# Qwiic_Chirp_101.net
KiCad netlist of a schematic drawn in EAGLE
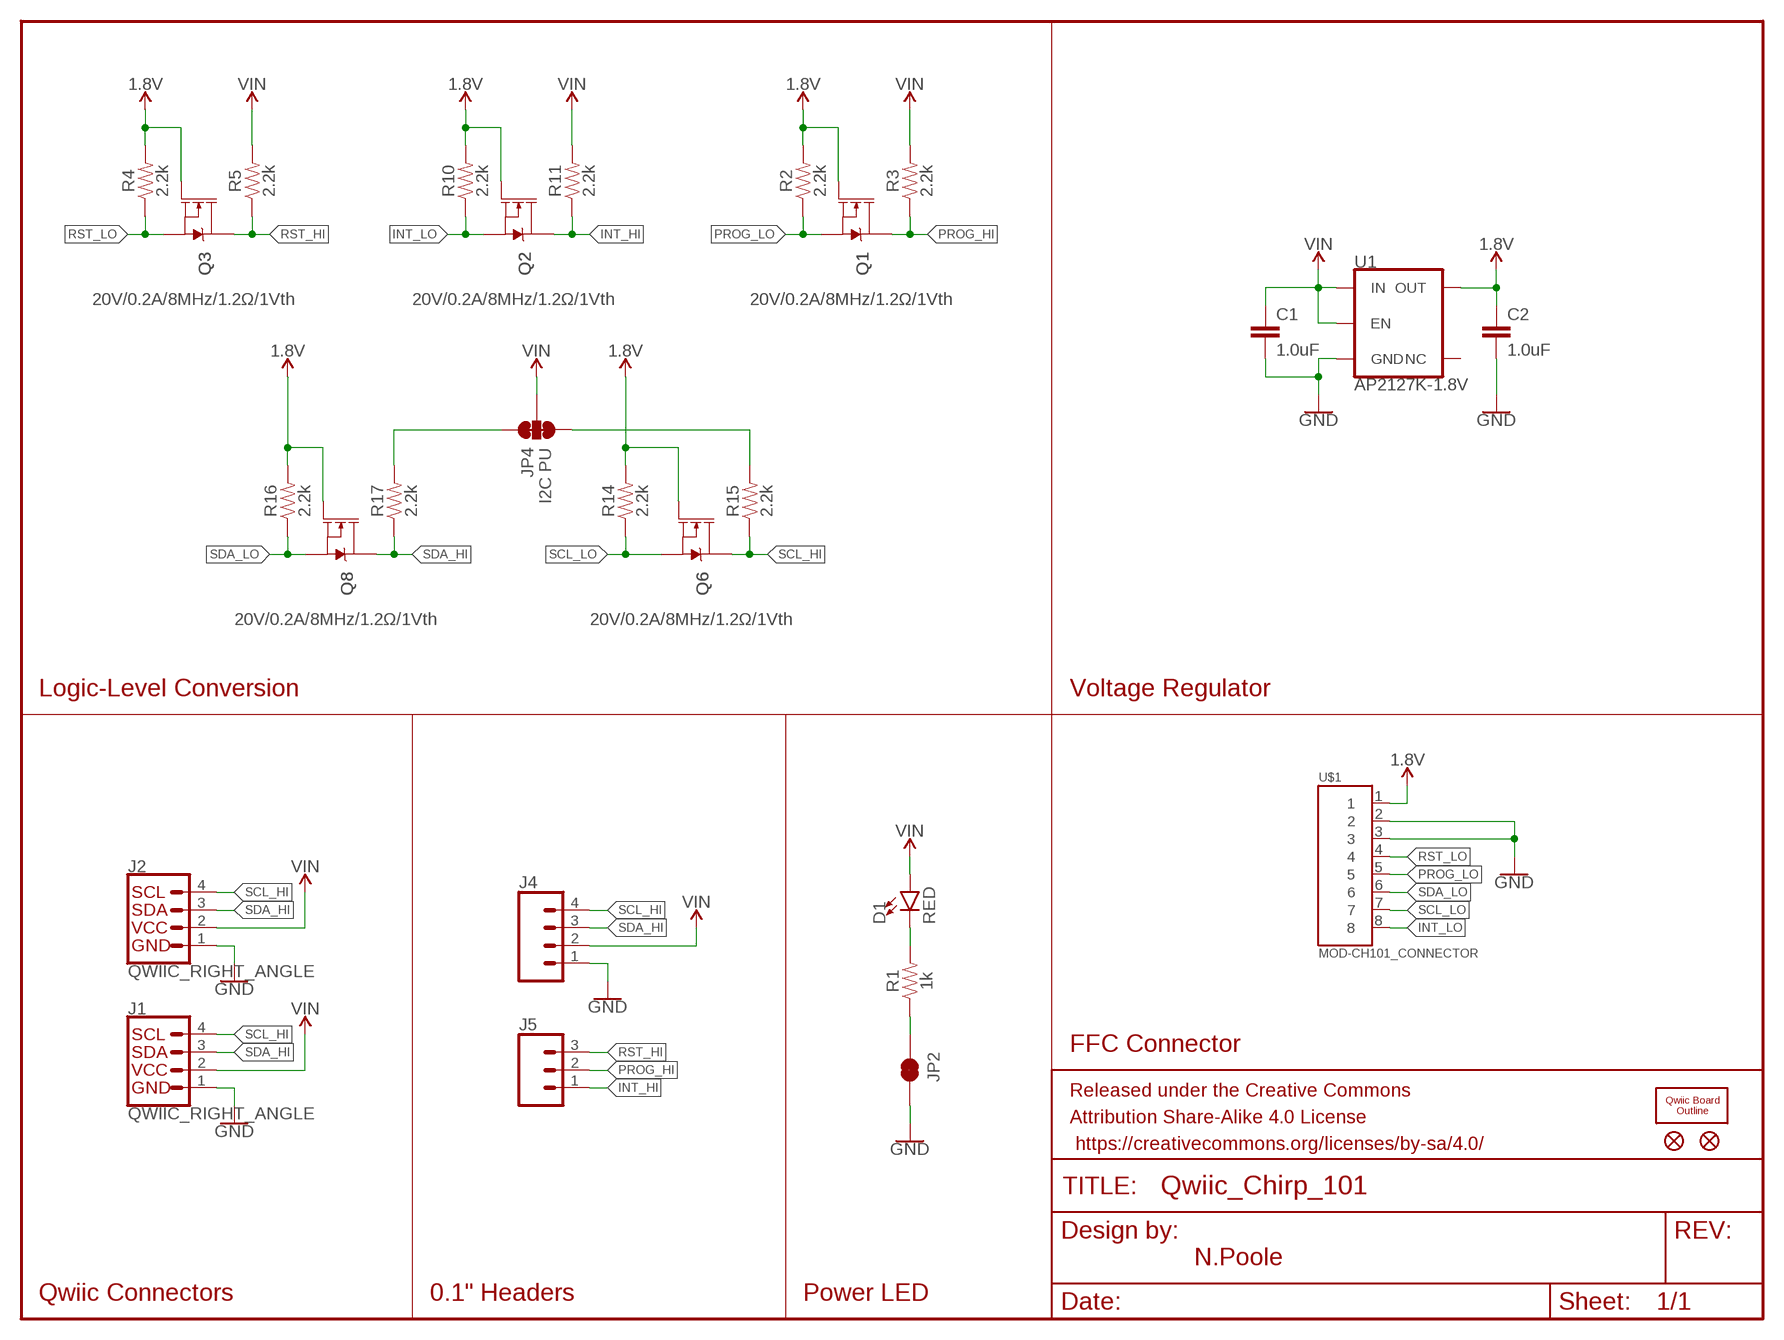
[diagram p0: schematic, sheet 1]

(export (version "E")
  (design (tool "Eeschema 10.0.6"))
  (components
    (comp (ref "C1")
      (value "1.0uF")
      (footprint "eagle-import:0603")
      (libsource (lib "eagle-import") (part "1.0UF-0603-16V-10%"))
    )
    (comp (ref "C2")
      (value "1.0uF")
      (footprint "eagle-import:0603")
      (libsource (lib "eagle-import") (part "1.0UF-0603-16V-10%"))
    )
    (comp (ref "D1")
      (value "RED")
      (footprint "eagle-import:LED-0603")
      (libsource (lib "eagle-import") (part "LED-RED0603"))
    )
    (comp (ref "FD1")
      (value "FIDUCIALUFIDUCIAL")
      (footprint "eagle-import:FIDUCIAL-MICRO")
      (libsource (lib "eagle-import") (part "FIDUCIALUFIDUCIAL"))
    )
    (comp (ref "FD2")
      (value "FIDUCIALUFIDUCIAL")
      (footprint "eagle-import:FIDUCIAL-MICRO")
      (libsource (lib "eagle-import") (part "FIDUCIALUFIDUCIAL"))
    )
    (comp (ref "FRAME1")
      (value "FRAME-LETTERNO_PACKAGE")
      (footprint "eagle-import:DUMMY")
      (fields (field (name "DESIGNER") "Nobody"))
      (libsource (lib "eagle-import") (part "FRAME-LETTERNO_PACKAGE"))
    )
    (comp (ref "J1")
      (value "QWIIC_RIGHT_ANGLE")
      (footprint "eagle-import:JST04_1MM_RA")
      (libsource (lib "eagle-import") (part "QWIIC_CONNECTORJS-1MM"))
    )
    (comp (ref "J2")
      (value "QWIIC_RIGHT_ANGLE")
      (footprint "eagle-import:JST04_1MM_RA")
      (libsource (lib "eagle-import") (part "QWIIC_CONNECTORJS-1MM"))
    )
    (comp (ref "J4")
      (value "CONN_041X04_NO_SILK")
      (footprint "eagle-import:1X04_NO_SILK")
      (libsource (lib "eagle-import") (part "CONN_041X04_NO_SILK"))
    )
    (comp (ref "J5")
      (value "CONN_031X03_NO_SILK")
      (footprint "eagle-import:1X03_NO_SILK")
      (libsource (lib "eagle-import") (part "CONN_031X03_NO_SILK"))
    )
    (comp (ref "JP2")
      (value "JUMPER-SMT_2_NC_TRACE_SILK")
      (footprint "eagle-import:SMT-JUMPER_2_NC_TRACE_SILK")
      (libsource (lib "eagle-import") (part "JUMPER-SMT_2_NC_TRACE_SILK"))
    )
    (comp (ref "JP4")
      (value "I2C PU")
      (footprint "eagle-import:SMT-JUMPER_3_2-NC_TRACE_SILK")
      (libsource (lib "eagle-import") (part "JUMPER-SMT_3_2-NC_TRACE_SILK"))
    )
    (comp (ref "Q1")
      (value "20V/0.2A/8MHz/1.2Ω/1Vth")
      (footprint "eagle-import:SOT-416FL")
      (libsource (lib "eagle-import") (part "MOSFET-NCH-RE1C002UN"))
    )
    (comp (ref "Q2")
      (value "20V/0.2A/8MHz/1.2Ω/1Vth")
      (footprint "eagle-import:SOT-416FL")
      (libsource (lib "eagle-import") (part "MOSFET-NCH-RE1C002UN"))
    )
    (comp (ref "Q3")
      (value "20V/0.2A/8MHz/1.2Ω/1Vth")
      (footprint "eagle-import:SOT-416FL")
      (libsource (lib "eagle-import") (part "MOSFET-NCH-RE1C002UN"))
    )
    (comp (ref "Q6")
      (value "20V/0.2A/8MHz/1.2Ω/1Vth")
      (footprint "eagle-import:SOT-416FL")
      (libsource (lib "eagle-import") (part "MOSFET-NCH-RE1C002UN"))
    )
    (comp (ref "Q8")
      (value "20V/0.2A/8MHz/1.2Ω/1Vth")
      (footprint "eagle-import:SOT-416FL")
      (libsource (lib "eagle-import") (part "MOSFET-NCH-RE1C002UN"))
    )
    (comp (ref "R1")
      (value "1k")
      (footprint "eagle-import:0603")
      (libsource (lib "eagle-import") (part "1KOHM-0603-1/10W-1%"))
    )
    (comp (ref "R2")
      (value "2.2k")
      (footprint "eagle-import:0402-TIGHT")
      (libsource (lib "eagle-import") (part "2.2KOHM-0402T-1/16W-1%"))
    )
    (comp (ref "R3")
      (value "2.2k")
      (footprint "eagle-import:0402-TIGHT")
      (libsource (lib "eagle-import") (part "2.2KOHM-0402T-1/16W-1%"))
    )
    (comp (ref "R4")
      (value "2.2k")
      (footprint "eagle-import:0402-TIGHT")
      (libsource (lib "eagle-import") (part "2.2KOHM-0402T-1/16W-1%"))
    )
    (comp (ref "R5")
      (value "2.2k")
      (footprint "eagle-import:0402-TIGHT")
      (libsource (lib "eagle-import") (part "2.2KOHM-0402T-1/16W-1%"))
    )
    (comp (ref "R10")
      (value "2.2k")
      (footprint "eagle-import:0402-TIGHT")
      (libsource (lib "eagle-import") (part "2.2KOHM-0402T-1/16W-1%"))
    )
    (comp (ref "R11")
      (value "2.2k")
      (footprint "eagle-import:0402-TIGHT")
      (libsource (lib "eagle-import") (part "2.2KOHM-0402T-1/16W-1%"))
    )
    (comp (ref "R14")
      (value "2.2k")
      (footprint "eagle-import:0402-TIGHT")
      (libsource (lib "eagle-import") (part "2.2KOHM-0402T-1/16W-1%"))
    )
    (comp (ref "R15")
      (value "2.2k")
      (footprint "eagle-import:0402-TIGHT")
      (libsource (lib "eagle-import") (part "2.2KOHM-0402T-1/16W-1%"))
    )
    (comp (ref "R16")
      (value "2.2k")
      (footprint "eagle-import:0402-TIGHT")
      (libsource (lib "eagle-import") (part "2.2KOHM-0402T-1/16W-1%"))
    )
    (comp (ref "R17")
      (value "2.2k")
      (footprint "eagle-import:0402-TIGHT")
      (libsource (lib "eagle-import") (part "2.2KOHM-0402T-1/16W-1%"))
    )
    (comp (ref "U$1")
      (value "MOD-CH101_CONNECTOR")
      (footprint "eagle-import:FPC_MOLEX5034800800")
      (libsource (lib "eagle-import") (part "MOD-CH101_CONNECTOR"))
    )
    (comp (ref "U$2")
      (value "QWIIC_BOARD_OUTLINEH")
      (footprint "eagle-import:QWIIC_BOARD_MOUNT_HOLES")
      (libsource (lib "eagle-import") (part "QWIIC_BOARD_OUTLINEH"))
    )
    (comp (ref "U1")
      (value "AP2127K-1.8V")
      (footprint "eagle-import:SOT23-5")
      (libsource (lib "eagle-import") (part "V_REG_AP2127K-1.8V"))
    )
  )
  (nets
    (net (code "1") (name "1.8V") (class "Default")
      (node (ref "C2") (pin "1") (pinfunction "1_1") (pintype "passive"))
      (node (ref "Q1") (pin "1") (pinfunction "G_1") (pintype "bidirectional"))
      (node (ref "Q2") (pin "1") (pinfunction "G_1") (pintype "bidirectional"))
      (node (ref "Q3") (pin "1") (pinfunction "G_1") (pintype "bidirectional"))
      (node (ref "Q6") (pin "1") (pinfunction "G_1") (pintype "bidirectional"))
      (node (ref "Q8") (pin "1") (pinfunction "G_1") (pintype "bidirectional"))
      (node (ref "R10") (pin "2") (pinfunction "2_2") (pintype "passive"))
      (node (ref "R14") (pin "2") (pinfunction "2_2") (pintype "passive"))
      (node (ref "R16") (pin "2") (pinfunction "2_2") (pintype "passive"))
      (node (ref "R2") (pin "2") (pinfunction "2_2") (pintype "passive"))
      (node (ref "R4") (pin "2") (pinfunction "2_2") (pintype "passive"))
      (node (ref "U$1") (pin "1") (pinfunction "1_1") (pintype "bidirectional"))
      (node (ref "U1") (pin "5") (pinfunction "OUT_5") (pintype "passive"))
    )
    (net (code "2") (name "GND") (class "Default")
      (node (ref "C1") (pin "2") (pinfunction "2_2") (pintype "passive"))
      (node (ref "C2") (pin "2") (pinfunction "2_2") (pintype "passive"))
      (node (ref "J1") (pin "1") (pinfunction "1_1") (pintype "power_in"))
      (node (ref "J2") (pin "1") (pinfunction "1_1") (pintype "power_in"))
      (node (ref "J4") (pin "1") (pinfunction "1_1") (pintype "passive"))
      (node (ref "JP2") (pin "2") (pinfunction "2_2") (pintype "passive"))
      (node (ref "U$1") (pin "2") (pinfunction "2_2") (pintype "bidirectional"))
      (node (ref "U$1") (pin "3") (pinfunction "3_3") (pintype "bidirectional"))
      (node (ref "U1") (pin "2") (pinfunction "GND_2") (pintype "input"))
    )
    (net (code "3") (name "INT_HI") (class "Default")
      (node (ref "J5") (pin "1") (pinfunction "1_1") (pintype "passive"))
      (node (ref "Q2") (pin "3") (pinfunction "D_3") (pintype "bidirectional"))
      (node (ref "R11") (pin "1") (pinfunction "1_1") (pintype "passive"))
    )
    (net (code "4") (name "INT_LO") (class "Default")
      (node (ref "Q2") (pin "2") (pinfunction "S_2") (pintype "bidirectional"))
      (node (ref "R10") (pin "1") (pinfunction "1_1") (pintype "passive"))
      (node (ref "U$1") (pin "8") (pinfunction "8_8") (pintype "bidirectional"))
    )
    (net (code "5") (name "Net-(D1-PadC)") (class "Default")
      (node (ref "D1") (pin "C") (pinfunction "C_C") (pintype "passive"))
      (node (ref "R1") (pin "2") (pinfunction "2_2") (pintype "passive"))
    )
    (net (code "6") (name "Net-(JP2-Pad1)") (class "Default")
      (node (ref "JP2") (pin "1") (pinfunction "1_1") (pintype "passive"))
      (node (ref "R1") (pin "1") (pinfunction "1_1") (pintype "passive"))
    )
    (net (code "7") (name "Net-(JP4-Pad1)") (class "Default")
      (node (ref "JP4") (pin "1") (pinfunction "1_1") (pintype "passive"))
      (node (ref "R17") (pin "2") (pinfunction "2_2") (pintype "passive"))
    )
    (net (code "8") (name "Net-(JP4-Pad3)") (class "Default")
      (node (ref "JP4") (pin "3") (pinfunction "3_3") (pintype "passive"))
      (node (ref "R15") (pin "2") (pinfunction "2_2") (pintype "passive"))
    )
    (net (code "9") (name "PROG_HI") (class "Default")
      (node (ref "J5") (pin "2") (pinfunction "2_2") (pintype "passive"))
      (node (ref "Q1") (pin "3") (pinfunction "D_3") (pintype "bidirectional"))
      (node (ref "R3") (pin "1") (pinfunction "1_1") (pintype "passive"))
    )
    (net (code "10") (name "PROG_LO") (class "Default")
      (node (ref "Q1") (pin "2") (pinfunction "S_2") (pintype "bidirectional"))
      (node (ref "R2") (pin "1") (pinfunction "1_1") (pintype "passive"))
      (node (ref "U$1") (pin "5") (pinfunction "5_5") (pintype "bidirectional"))
    )
    (net (code "11") (name "RST_HI") (class "Default")
      (node (ref "J5") (pin "3") (pinfunction "3_3") (pintype "passive"))
      (node (ref "Q3") (pin "3") (pinfunction "D_3") (pintype "bidirectional"))
      (node (ref "R5") (pin "1") (pinfunction "1_1") (pintype "passive"))
    )
    (net (code "12") (name "RST_LO") (class "Default")
      (node (ref "Q3") (pin "2") (pinfunction "S_2") (pintype "bidirectional"))
      (node (ref "R4") (pin "1") (pinfunction "1_1") (pintype "passive"))
      (node (ref "U$1") (pin "4") (pinfunction "4_4") (pintype "bidirectional"))
    )
    (net (code "13") (name "SCL_HI") (class "Default")
      (node (ref "J1") (pin "4") (pinfunction "4_4") (pintype "passive"))
      (node (ref "J2") (pin "4") (pinfunction "4_4") (pintype "passive"))
      (node (ref "J4") (pin "4") (pinfunction "4_4") (pintype "passive"))
      (node (ref "Q6") (pin "3") (pinfunction "D_3") (pintype "bidirectional"))
      (node (ref "R15") (pin "1") (pinfunction "1_1") (pintype "passive"))
    )
    (net (code "14") (name "SCL_LO") (class "Default")
      (node (ref "Q6") (pin "2") (pinfunction "S_2") (pintype "bidirectional"))
      (node (ref "R14") (pin "1") (pinfunction "1_1") (pintype "passive"))
      (node (ref "U$1") (pin "7") (pinfunction "7_7") (pintype "bidirectional"))
    )
    (net (code "15") (name "SDA_HI") (class "Default")
      (node (ref "J1") (pin "3") (pinfunction "3_3") (pintype "passive"))
      (node (ref "J2") (pin "3") (pinfunction "3_3") (pintype "passive"))
      (node (ref "J4") (pin "3") (pinfunction "3_3") (pintype "passive"))
      (node (ref "Q8") (pin "3") (pinfunction "D_3") (pintype "bidirectional"))
      (node (ref "R17") (pin "1") (pinfunction "1_1") (pintype "passive"))
    )
    (net (code "16") (name "SDA_LO") (class "Default")
      (node (ref "Q8") (pin "2") (pinfunction "S_2") (pintype "bidirectional"))
      (node (ref "R16") (pin "1") (pinfunction "1_1") (pintype "passive"))
      (node (ref "U$1") (pin "6") (pinfunction "6_6") (pintype "bidirectional"))
    )
    (net (code "17") (name "VIN") (class "Default")
      (node (ref "C1") (pin "1") (pinfunction "1_1") (pintype "passive"))
      (node (ref "D1") (pin "A") (pinfunction "A_A") (pintype "passive"))
      (node (ref "J1") (pin "2") (pinfunction "2_2") (pintype "power_in"))
      (node (ref "J2") (pin "2") (pinfunction "2_2") (pintype "power_in"))
      (node (ref "J4") (pin "2") (pinfunction "2_2") (pintype "passive"))
      (node (ref "JP4") (pin "2") (pinfunction "2_2") (pintype "passive"))
      (node (ref "R11") (pin "2") (pinfunction "2_2") (pintype "passive"))
      (node (ref "R3") (pin "2") (pinfunction "2_2") (pintype "passive"))
      (node (ref "R5") (pin "2") (pinfunction "2_2") (pintype "passive"))
      (node (ref "U1") (pin "1") (pinfunction "IN_1") (pintype "input"))
      (node (ref "U1") (pin "3") (pinfunction "EN_3") (pintype "input"))
    )
    (net (code "18") (name "unconnected-(U1-NC-Pad4)") (class "Default")
      (node (ref "U1") (pin "4") (pinfunction "NC_4") (pintype "no_connect"))
    )
  )
)
